# ISD4004.net
KiCad netlist of a schematic drawn in Altium Designer
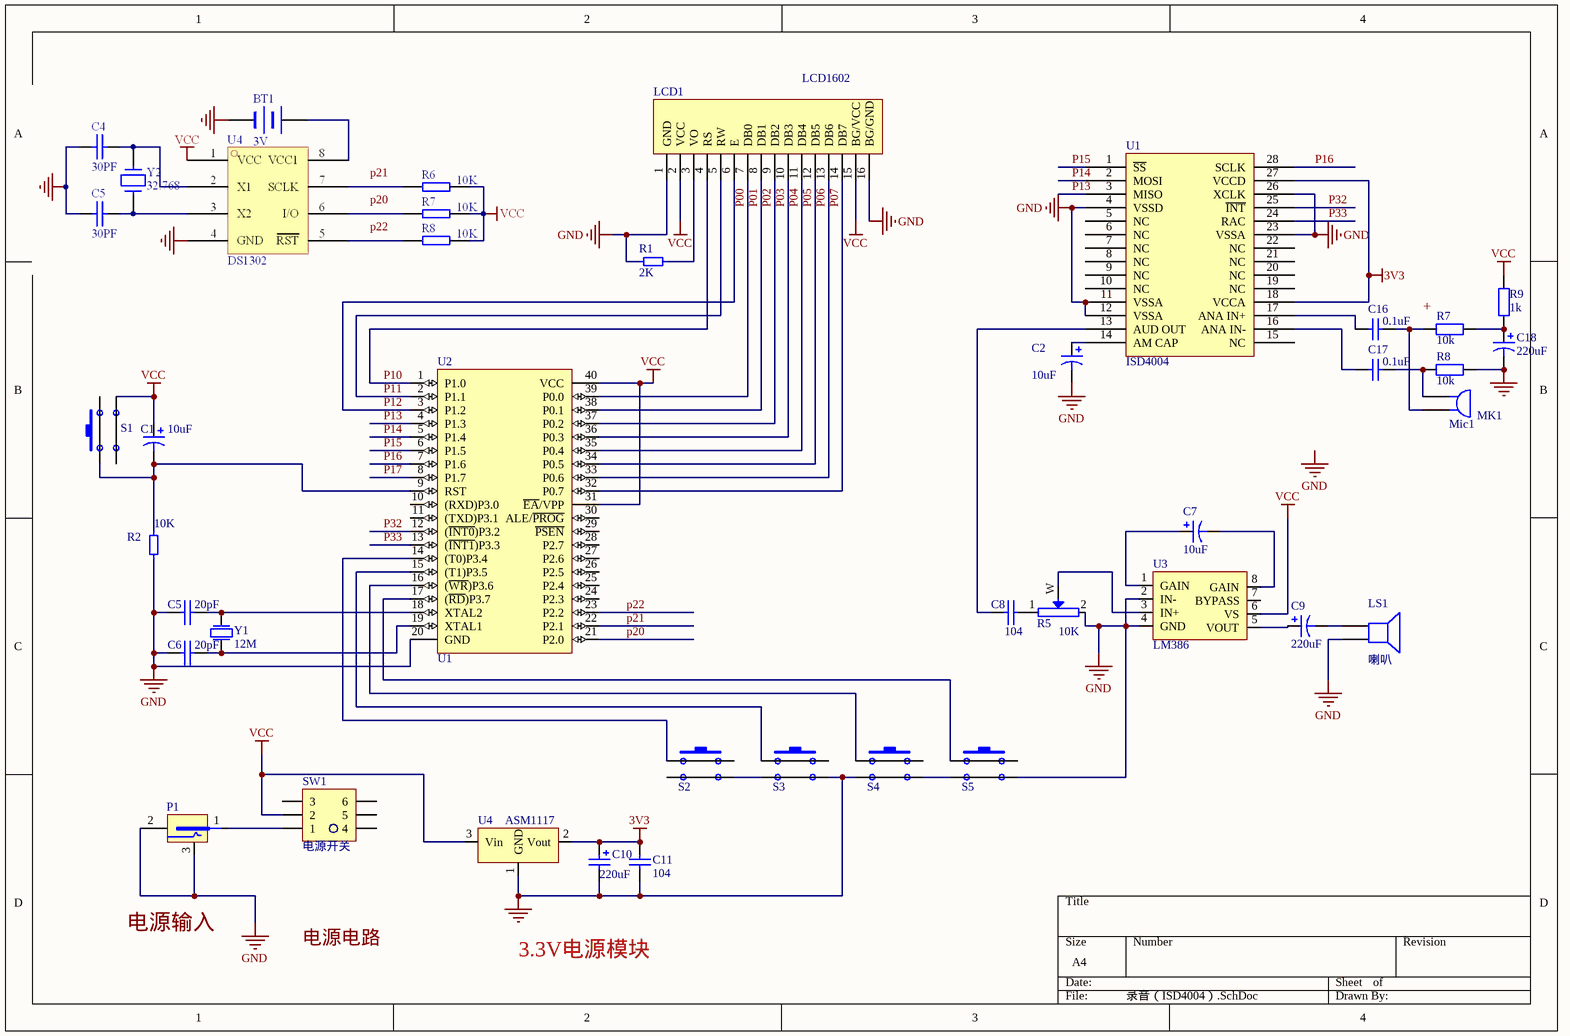
[diagram p0: 录音（ISD4004）.SchDoc]

(export (version "E")
  (design (tool "Eeschema 10.0.6"))
  (components
    (comp (ref "C1")
      (value "10uF")
      (footprint "C_10")
      (description "Polarized Capacitor (Radial)")
      (fields (field (name "PUBLISHER") "Altium Limited"))
      (libsource (lib "简易动环监控系统") (part "Cap Pol1"))
    )
    (comp (ref "C2")
      (value "10uF")
      (footprint "C_10")
      (description "Polarized Capacitor (Radial)")
      (fields (field (name "PUBLISHER") "Altium Limited"))
      (libsource (lib "简易动环监控系统") (part "Cap Pol1"))
    )
    (comp (ref "C5")
      (value "20pF")
      (footprint "CAP CP")
      (description "电容")
      (libsource (lib "C8051F020最小2") (part "CAP"))
    )
    (comp (ref "C6")
      (value "20pF")
      (footprint "CAP CP")
      (description "电容")
      (libsource (lib "C8051F020最小2") (part "CAP"))
    )
    (comp (ref "C7")
      (value "10uF")
      (footprint "CAP_470")
      (description "Polarized Capacitor (Radial)")
      (fields (field (name "PUBLISHER") "Altium Limited"))
      (libsource (lib "简易动环监控系统") (part "Cap Pol1"))
    )
    (comp (ref "C8")
      (value "104")
      (footprint "CAP5")
      (description "电容")
      (libsource (lib "C8051F020最小2") (part "CAP"))
    )
    (comp (ref "C9")
      (value "220uF")
      (footprint "CAP_470")
      (description "Polarized Capacitor (Radial)")
      (fields (field (name "PUBLISHER") "Altium Limited"))
      (libsource (lib "简易动环监控系统") (part "Cap Pol1"))
    )
    (comp (ref "C10")
      (value "220uF")
      (footprint "C_10")
      (description "220uF 470uF 外径8mm 引脚3mm")
      (fields (field (name "Comment") "220uf"))
      (libsource (lib "*") (part "CAP 470uF"))
    )
    (comp (ref "C11")
      (value "104")
      (footprint "CAP CP")
      (description "瓷片电容")
      (libsource (lib "*") (part "CAP"))
    )
    (comp (ref "C16")
      (value "0.1uF")
      (footprint "瓷片电容0.3")
      (description "Capacitor")
      (fields (field (name "PUBLISHER") "Altium Limited"))
      (libsource (lib "Miscellaneous Devices") (part "Cap"))
    )
    (comp (ref "C17")
      (value "0.1uF")
      (footprint "瓷片电容0.3")
      (description "Capacitor")
      (fields (field (name "PUBLISHER") "Altium Limited"))
      (libsource (lib "Miscellaneous Devices") (part "Cap"))
    )
    (comp (ref "C18")
      (value "220uF")
      (footprint "电容0.5")
      (description "Polarized Capacitor (Radial)")
      (fields (field (name "PUBLISHER") "Altium Limited"))
      (libsource (lib "Miscellaneous Devices") (part "Cap Pol1"))
    )
    (comp (ref "LCD1") (value "LCD1602") (footprint "1602") (libsource (lib "实用原理图库") (part "LCD1602")))
    (comp (ref "LS1")
      (value "喇叭")
      (footprint "SIP2")
      (description "Loudspeaker")
      (fields (field (name "PUBLISHER") "Altium Limited"))
      (libsource (lib "Miscellaneous Devices") (part "Speaker"))
    )
    (comp (ref "MK1")
      (value "Mic1")
      (footprint "PIN2")
      (description "Microphone")
      (fields (field (name "PUBLISHER") "Altium Limited"))
      (libsource (lib "Miscellaneous Devices") (part "Mic1"))
    )
    (comp (ref "P1") (value "电源输入") (footprint "DC2.1") (libsource (lib "我自己的") (part "POWER")))
    (comp (ref "R1") (value "2K") (footprint "AXIAL0.3") (libsource (lib "C8051F020最小2") (part "RES2")))
    (comp (ref "R2") (value "10K") (footprint "AXIAL0.3") (libsource (lib "C8051F020最小2") (part "RES2")))
    (comp (ref "R5")
      (value "10K")
      (footprint "RES")
      (description "可调电位器")
      (fields (field (name "Comment") "RES  KB"))
      (libsource (lib "JIANYANG") (part "RES  KB"))
    )
    (comp (ref "R7")
      (value "10k")
      (footprint "AXIAL-0.4")
      (description "Resistor")
      (fields (field (name "PUBLISHER") "Altium Limited"))
      (libsource (lib "") (part "Res2_1"))
    )
    (comp (ref "R8")
      (value "10k")
      (footprint "AXIAL-0.4")
      (description "Resistor")
      (fields (field (name "PUBLISHER") "Altium Limited"))
      (libsource (lib "") (part "Res2_1"))
    )
    (comp (ref "R9")
      (value "1k")
      (footprint "AXIAL-0.4")
      (description "Resistor")
      (fields (field (name "PUBLISHER") "Altium Limited"))
      (libsource (lib "Miscellaneous Devices") (part "Res2"))
    )
    (comp (ref "S1") (value "SW") (footprint "key") (libsource (lib "我自己的") (part "SW1_key")))
    (comp (ref "S2") (value "SW") (footprint "key") (libsource (lib "我自己的") (part "SW1_key")))
    (comp (ref "S3") (value "SW") (footprint "key") (libsource (lib "我自己的") (part "SW1_key")))
    (comp (ref "S4") (value "SW") (footprint "key") (libsource (lib "我自己的") (part "SW1_key")))
    (comp (ref "S5") (value "SW") (footprint "key") (libsource (lib "我自己的") (part "SW1_key")))
    (comp (ref "SW1") (value "电源开关") (footprint "sw_自锁 1") (libsource (lib "我自己的") (part "SW1")))
    (comp (ref "U1") (value "ISD4004") (footprint "DIP28") (libsource (lib "*") (part "ISD4004")))
    (comp (ref "U2") (value "U1") (footprint "DIP40 - 做板") (libsource (lib "实验板原理图") (part "U1")))
    (comp (ref "U3") (value "LM386") (footprint "DIP8") (libsource (lib "我自己的") (part "LM386")))
    (comp (ref "U4") (value "ASM1117") (footprint "ASM1117") (libsource (lib "*") (part "ASM1117")))
    (comp (ref "Y1")
      (value "12M")
      (footprint "XTAL")
      (description "Crystal Oscillator")
      (libsource (lib "C8051F020最小2") (part "16M"))
    )
  )
  (nets
    (net (code "2") (name "/P00") (class "Default")
      (node (ref "LCD1") (pin "7") (pinfunction "DB0_7") (pintype "passive"))
      (node (ref "U2") (pin "39") (pinfunction "P0.0_39") (pintype "bidirectional"))
    )
    (net (code "3") (name "/P01") (class "Default")
      (node (ref "LCD1") (pin "8") (pinfunction "DB1_8") (pintype "passive"))
      (node (ref "U2") (pin "38") (pinfunction "P0.1_38") (pintype "bidirectional"))
    )
    (net (code "4") (name "/P02") (class "Default")
      (node (ref "LCD1") (pin "9") (pinfunction "DB2_9") (pintype "passive"))
      (node (ref "U2") (pin "37") (pinfunction "P0.2_37") (pintype "bidirectional"))
    )
    (net (code "5") (name "/P03") (class "Default")
      (node (ref "LCD1") (pin "10") (pinfunction "DB3_10") (pintype "passive"))
      (node (ref "U2") (pin "36") (pinfunction "P0.3_36") (pintype "bidirectional"))
    )
    (net (code "6") (name "/P04") (class "Default")
      (node (ref "LCD1") (pin "11") (pinfunction "DB4_11") (pintype "passive"))
      (node (ref "U2") (pin "35") (pinfunction "P0.4_35") (pintype "bidirectional"))
    )
    (net (code "7") (name "/P05") (class "Default")
      (node (ref "LCD1") (pin "12") (pinfunction "DB5_12") (pintype "passive"))
      (node (ref "U2") (pin "34") (pinfunction "P0.5_34") (pintype "bidirectional"))
    )
    (net (code "8") (name "/P06") (class "Default")
      (node (ref "LCD1") (pin "13") (pinfunction "DB6_13") (pintype "passive"))
      (node (ref "U2") (pin "33") (pinfunction "P0.6_33") (pintype "bidirectional"))
    )
    (net (code "9") (name "/P07") (class "Default")
      (node (ref "LCD1") (pin "14") (pinfunction "DB7_14") (pintype "passive"))
      (node (ref "U2") (pin "32") (pinfunction "P0.7_32") (pintype "bidirectional"))
    )
    (net (code "10") (name "/P10") (class "Default")
      (node (ref "LCD1") (pin "4") (pinfunction "RS_4") (pintype "passive"))
      (node (ref "U2") (pin "1") (pinfunction "P1.0_1") (pintype "bidirectional"))
    )
    (net (code "11") (name "/P11") (class "Default")
      (node (ref "LCD1") (pin "5") (pinfunction "RW_5") (pintype "passive"))
      (node (ref "U2") (pin "2") (pinfunction "P1.1_2") (pintype "bidirectional"))
    )
    (net (code "12") (name "/P12") (class "Default")
      (node (ref "LCD1") (pin "6") (pinfunction "E_6") (pintype "passive"))
      (node (ref "U2") (pin "3") (pinfunction "P1.2_3") (pintype "bidirectional"))
    )
    (net (code "13") (name "/P13") (class "Default")
      (node (ref "U1") (pin "3") (pinfunction "MISO_3") (pintype "passive"))
      (node (ref "U2") (pin "4") (pinfunction "P1.3_4") (pintype "bidirectional"))
    )
    (net (code "14") (name "/P14") (class "Default")
      (node (ref "U1") (pin "2") (pinfunction "MOSI_2") (pintype "passive"))
      (node (ref "U2") (pin "5") (pinfunction "P1.4_5") (pintype "bidirectional"))
    )
    (net (code "15") (name "/P15") (class "Default")
      (node (ref "U1") (pin "1") (pinfunction "~{SS}_1") (pintype "passive"))
      (node (ref "U2") (pin "6") (pinfunction "P1.5_6") (pintype "bidirectional"))
    )
    (net (code "16") (name "/P16") (class "Default")
      (node (ref "U1") (pin "28") (pinfunction "SCLK_28") (pintype "passive"))
      (node (ref "U2") (pin "7") (pinfunction "P1.6_7") (pintype "bidirectional"))
    )
    (net (code "17") (name "/P17") (class "Default")
      (node (ref "U2") (pin "8") (pinfunction "P1.7_8") (pintype "bidirectional"))
    )
    (net (code "18") (name "/P32") (class "Default")
      (node (ref "U1") (pin "25") (pinfunction "~{INT}_25") (pintype "passive"))
      (node (ref "U2") (pin "12") (pinfunction "(~{INT0})P3.2_12") (pintype "bidirectional"))
    )
    (net (code "19") (name "/P33") (class "Default")
      (node (ref "U1") (pin "24") (pinfunction "RAC_24") (pintype "passive"))
      (node (ref "U2") (pin "13") (pinfunction "(~{INT1})P3.3_13") (pintype "bidirectional"))
    )
    (net (code "20") (name "/p20") (class "Default")
      (node (ref "U2") (pin "21") (pinfunction "P2.0_21") (pintype "bidirectional"))
    )
    (net (code "21") (name "/p21") (class "Default")
      (node (ref "U2") (pin "22") (pinfunction "P2.1_22") (pintype "bidirectional"))
    )
    (net (code "22") (name "/p22") (class "Default")
      (node (ref "U2") (pin "23") (pinfunction "P2.2_23") (pintype "bidirectional"))
    )
    (net (code "25") (name "3V3") (class "Default")
      (node (ref "C10") (pin "1") (pinfunction "1_1") (pintype "passive"))
      (node (ref "C11") (pin "2") (pinfunction "2_2") (pintype "passive"))
      (node (ref "U1") (pin "18") (pinfunction "VCCA_18") (pintype "passive"))
      (node (ref "U1") (pin "27") (pinfunction "VCCD_27") (pintype "passive"))
      (node (ref "U4") (pin "2") (pinfunction "Vout_2") (pintype "passive"))
    )
    (net (code "26") (name "GND") (class "Default")
      (node (ref "C10") (pin "2") (pinfunction "2_2") (pintype "passive"))
      (node (ref "C11") (pin "1") (pinfunction "1_1") (pintype "passive"))
      (node (ref "C18") (pin "2") (pinfunction "2_2") (pintype "passive"))
      (node (ref "C2") (pin "2") (pinfunction "2_2") (pintype "passive"))
      (node (ref "C5") (pin "1") (pinfunction "1_1") (pintype "passive"))
      (node (ref "C6") (pin "1") (pinfunction "1_1") (pintype "passive"))
      (node (ref "LCD1") (pin "1") (pinfunction "GND_1") (pintype "passive"))
      (node (ref "LCD1") (pin "16") (pinfunction "BG/GND_16") (pintype "passive"))
      (node (ref "LS1") (pin "2") (pinfunction "2_2") (pintype "passive"))
      (node (ref "P1") (pin "2") (pintype "passive"))
      (node (ref "P1") (pin "3") (pintype "passive"))
      (node (ref "R1") (pin "1") (pinfunction "1_1") (pintype "passive"))
      (node (ref "R2") (pin "1") (pinfunction "1_1") (pintype "passive"))
      (node (ref "R5") (pin "2") (pintype "passive"))
      (node (ref "R8") (pin "2") (pinfunction "2_2") (pintype "passive"))
      (node (ref "S3") (pin "2") (pinfunction "2_2") (pintype "passive"))
      (node (ref "S4") (pin "2") (pinfunction "2_2") (pintype "passive"))
      (node (ref "S5") (pin "2") (pinfunction "2_2") (pintype "passive"))
      (node (ref "U1") (pin "11") (pinfunction "VSSA_11") (pintype "passive"))
      (node (ref "U1") (pin "12") (pinfunction "VSSA_12") (pintype "passive"))
      (node (ref "U1") (pin "23") (pinfunction "VSSA_23") (pintype "passive"))
      (node (ref "U1") (pin "26") (pinfunction "XCLK_26") (pintype "passive"))
      (node (ref "U1") (pin "4") (pinfunction "VSSD_4") (pintype "passive"))
      (node (ref "U2") (pin "20") (pinfunction "GND_20") (pintype "power_in"))
      (node (ref "U3") (pin "2") (pinfunction "IN-_2") (pintype "passive"))
      (node (ref "U3") (pin "4") (pinfunction "GND_4") (pintype "passive"))
      (node (ref "U4") (pin "1") (pinfunction "GND_1") (pintype "passive"))
    )
    (net (code "27") (name "Net-(C7-Pad1)") (class "Default")
      (node (ref "C7") (pin "1") (pinfunction "1_1") (pintype "passive"))
      (node (ref "U3") (pin "1") (pinfunction "GAIN_1") (pintype "passive"))
    )
    (net (code "28") (name "Net-(C7-Pad2)") (class "Default")
      (node (ref "C7") (pin "2") (pinfunction "2_2") (pintype "passive"))
      (node (ref "U3") (pin "8") (pinfunction "GAIN_8") (pintype "passive"))
    )
    (net (code "29") (name "Net-(C8-Pad2)") (class "Default")
      (node (ref "C8") (pin "2") (pinfunction "2_2") (pintype "passive"))
      (node (ref "R5") (pin "1") (pintype "passive"))
    )
    (net (code "30") (name "Net-(C9-Pad2)") (class "Default")
      (node (ref "C9") (pin "2") (pinfunction "2_2") (pintype "passive"))
      (node (ref "LS1") (pin "1") (pinfunction "1_1") (pintype "passive"))
    )
    (net (code "31") (name "Net-(C16-Pad2)") (class "Default")
      (node (ref "C16") (pin "2") (pinfunction "2_2") (pintype "passive"))
      (node (ref "MK1") (pin "2") (pinfunction "2_2") (pintype "passive"))
      (node (ref "R7") (pin "1") (pinfunction "1_1") (pintype "passive"))
    )
    (net (code "32") (name "Net-(C17-Pad2)") (class "Default")
      (node (ref "C17") (pin "2") (pinfunction "2_2") (pintype "passive"))
      (node (ref "MK1") (pin "1") (pinfunction "1_1") (pintype "passive"))
      (node (ref "R8") (pin "1") (pinfunction "1_1") (pintype "passive"))
    )
    (net (code "33") (name "Net-(C18-Pad1)") (class "Default")
      (node (ref "C18") (pin "1") (pinfunction "1_1") (pintype "passive"))
      (node (ref "R7") (pin "2") (pinfunction "2_2") (pintype "passive"))
      (node (ref "R9") (pin "1") (pinfunction "1_1") (pintype "passive"))
    )
    (net (code "34") (name "Net-(LCD1-VO)") (class "Default")
      (node (ref "LCD1") (pin "3") (pinfunction "VO_3") (pintype "passive"))
      (node (ref "R1") (pin "2") (pinfunction "2_2") (pintype "passive"))
    )
    (net (code "35") (name "Net-(P1-Pad1)") (class "Default")
      (node (ref "P1") (pin "1") (pintype "passive"))
      (node (ref "SW1") (pin "1") (pinfunction "1_1") (pintype "passive"))
    )
    (net (code "36") (name "Net-(S2-Pad2)") (class "Default")
      (node (ref "S2") (pin "2") (pinfunction "2_2") (pintype "passive"))
      (node (ref "S3") (pin "2") (pinfunction "2_2") (pintype "passive"))
    )
    (net (code "37") (name "Net-(S4-Pad2)") (class "Default")
      (node (ref "S4") (pin "2") (pinfunction "2_2") (pintype "passive"))
      (node (ref "S5") (pin "2") (pinfunction "2_2") (pintype "passive"))
    )
    (net (code "38") (name "Net-(U1-AM_CAP)") (class "Default")
      (node (ref "C2") (pin "1") (pinfunction "1_1") (pintype "passive"))
      (node (ref "U1") (pin "14") (pinfunction "AM_CAP_14") (pintype "passive"))
    )
    (net (code "39") (name "Net-(U1-ANA_IN+)") (class "Default")
      (node (ref "C16") (pin "1") (pinfunction "1_1") (pintype "passive"))
      (node (ref "U1") (pin "17") (pinfunction "ANA_IN+_17") (pintype "passive"))
    )
    (net (code "40") (name "Net-(U1-ANA_IN-)") (class "Default")
      (node (ref "C17") (pin "1") (pinfunction "1_1") (pintype "passive"))
      (node (ref "U1") (pin "16") (pinfunction "ANA_IN-_16") (pintype "passive"))
    )
    (net (code "41") (name "Net-(U1-AUD_OUT)") (class "Default")
      (node (ref "C8") (pin "1") (pinfunction "1_1") (pintype "passive"))
      (node (ref "U1") (pin "13") (pinfunction "AUD_OUT_13") (pintype "passive"))
    )
    (net (code "42") (name "Net-(U2-(T0)P3.4)") (class "Default")
      (node (ref "S2") (pin "1") (pinfunction "1_1") (pintype "passive"))
      (node (ref "U2") (pin "14") (pinfunction "(T0)P3.4_14") (pintype "bidirectional"))
    )
    (net (code "43") (name "Net-(U2-(T1)P3.5)") (class "Default")
      (node (ref "S3") (pin "1") (pinfunction "1_1") (pintype "passive"))
      (node (ref "U2") (pin "15") (pinfunction "(T1)P3.5_15") (pintype "bidirectional"))
    )
    (net (code "44") (name "Net-(U2-(~{RD})P3.7)") (class "Default")
      (node (ref "S5") (pin "1") (pinfunction "1_1") (pintype "passive"))
      (node (ref "U2") (pin "17") (pinfunction "(~{RD})P3.7_17") (pintype "bidirectional"))
    )
    (net (code "45") (name "Net-(U2-(~{WR})P3.6)") (class "Default")
      (node (ref "S4") (pin "1") (pinfunction "1_1") (pintype "passive"))
      (node (ref "U2") (pin "16") (pinfunction "(~{WR})P3.6_16") (pintype "bidirectional"))
    )
    (net (code "46") (name "Net-(U2-RST)") (class "Default")
      (node (ref "C1") (pin "2") (pinfunction "2_2") (pintype "passive"))
      (node (ref "R2") (pin "2") (pinfunction "2_2") (pintype "passive"))
      (node (ref "S1") (pin "1") (pinfunction "1_1") (pintype "passive"))
      (node (ref "U2") (pin "9") (pinfunction "RST_9") (pintype "bidirectional"))
    )
    (net (code "47") (name "Net-(U2-XTAL1)") (class "Default")
      (node (ref "C6") (pin "2") (pinfunction "2_2") (pintype "passive"))
      (node (ref "U2") (pin "19") (pinfunction "XTAL1_19") (pintype "bidirectional"))
      (node (ref "Y1") (pin "2") (pinfunction "P2_2") (pintype "passive"))
    )
    (net (code "48") (name "Net-(U2-XTAL2)") (class "Default")
      (node (ref "C5") (pin "2") (pinfunction "2_2") (pintype "passive"))
      (node (ref "U2") (pin "18") (pinfunction "XTAL2_18") (pintype "bidirectional"))
      (node (ref "Y1") (pin "1") (pinfunction "P1_1") (pintype "passive"))
    )
    (net (code "49") (name "Net-(U3-IN+)") (class "Default")
      (node (ref "R5") (pin "W") (pintype "passive"))
      (node (ref "U3") (pin "3") (pinfunction "IN+_3") (pintype "passive"))
    )
    (net (code "50") (name "Net-(U3-VOUT)") (class "Default")
      (node (ref "C9") (pin "1") (pinfunction "1_1") (pintype "passive"))
      (node (ref "U3") (pin "5") (pinfunction "VOUT_5") (pintype "passive"))
    )
    (net (code "51") (name "VCC") (class "Default")
      (node (ref "C1") (pin "1") (pinfunction "1_1") (pintype "passive"))
      (node (ref "LCD1") (pin "15") (pinfunction "BG/VCC_15") (pintype "passive"))
      (node (ref "LCD1") (pin "2") (pinfunction "VCC_2") (pintype "passive"))
      (node (ref "R9") (pin "2") (pinfunction "2_2") (pintype "passive"))
      (node (ref "S1") (pin "2") (pinfunction "2_2") (pintype "passive"))
      (node (ref "SW1") (pin "2") (pinfunction "2_2") (pintype "passive"))
      (node (ref "U2") (pin "31") (pinfunction "~{EA}/VPP_31") (pintype "power_in"))
      (node (ref "U2") (pin "40") (pinfunction "VCC_40") (pintype "power_in"))
      (node (ref "U3") (pin "6") (pinfunction "VS_6") (pintype "passive"))
      (node (ref "U4") (pin "3") (pinfunction "Vin_3") (pintype "passive"))
    )
    (net (code "52") (name "unconnected-(S1-Pad1)") (class "Default")
      (node (ref "S1") (pin "1") (pinfunction "1_1") (pintype "passive"))
    )
    (net (code "53") (name "unconnected-(S1-Pad2)") (class "Default")
      (node (ref "S1") (pin "2") (pinfunction "2_2") (pintype "passive"))
    )
    (net (code "54") (name "unconnected-(S2-Pad1)") (class "Default")
      (node (ref "S2") (pin "1") (pinfunction "1_1") (pintype "passive"))
    )
    (net (code "55") (name "unconnected-(S2-Pad2)_1") (class "Default")
      (node (ref "S2") (pin "2") (pinfunction "2_2") (pintype "passive"))
    )
    (net (code "56") (name "unconnected-(S3-Pad1)") (class "Default")
      (node (ref "S3") (pin "1") (pinfunction "1_1") (pintype "passive"))
    )
    (net (code "57") (name "unconnected-(S4-Pad1)") (class "Default")
      (node (ref "S4") (pin "1") (pinfunction "1_1") (pintype "passive"))
    )
    (net (code "58") (name "unconnected-(S5-Pad1)") (class "Default")
      (node (ref "S5") (pin "1") (pinfunction "1_1") (pintype "passive"))
    )
    (net (code "59") (name "unconnected-(SW1-Pad3)") (class "Default")
      (node (ref "SW1") (pin "3") (pinfunction "3_3") (pintype "passive"))
    )
    (net (code "60") (name "unconnected-(SW1-Pad4)") (class "Default")
      (node (ref "SW1") (pin "4") (pinfunction "4_4") (pintype "passive"))
    )
    (net (code "61") (name "unconnected-(SW1-Pad5)") (class "Default")
      (node (ref "SW1") (pin "5") (pinfunction "5_5") (pintype "passive"))
    )
    (net (code "62") (name "unconnected-(SW1-Pad6)") (class "Default")
      (node (ref "SW1") (pin "6") (pinfunction "6_6") (pintype "passive"))
    )
    (net (code "63") (name "unconnected-(U1-NC-Pad5)") (class "Default")
      (node (ref "U1") (pin "5") (pinfunction "NC_5") (pintype "passive"))
    )
    (net (code "64") (name "unconnected-(U1-NC-Pad6)") (class "Default")
      (node (ref "U1") (pin "6") (pinfunction "NC_6") (pintype "passive"))
    )
    (net (code "65") (name "unconnected-(U1-NC-Pad7)") (class "Default")
      (node (ref "U1") (pin "7") (pinfunction "NC_7") (pintype "passive"))
    )
    (net (code "66") (name "unconnected-(U1-NC-Pad8)") (class "Default")
      (node (ref "U1") (pin "8") (pinfunction "NC_8") (pintype "passive"))
    )
    (net (code "67") (name "unconnected-(U1-NC-Pad9)") (class "Default")
      (node (ref "U1") (pin "9") (pinfunction "NC_9") (pintype "passive"))
    )
    (net (code "68") (name "unconnected-(U1-NC-Pad10)") (class "Default")
      (node (ref "U1") (pin "10") (pinfunction "NC_10") (pintype "passive"))
    )
    (net (code "69") (name "unconnected-(U1-NC-Pad15)") (class "Default")
      (node (ref "U1") (pin "15") (pinfunction "NC_15") (pintype "passive"))
    )
    (net (code "70") (name "unconnected-(U1-NC-Pad19)") (class "Default")
      (node (ref "U1") (pin "19") (pinfunction "NC_19") (pintype "passive"))
    )
    (net (code "71") (name "unconnected-(U1-NC-Pad20)") (class "Default")
      (node (ref "U1") (pin "20") (pinfunction "NC_20") (pintype "passive"))
    )
    (net (code "72") (name "unconnected-(U1-NC-Pad21)") (class "Default")
      (node (ref "U1") (pin "21") (pinfunction "NC_21") (pintype "passive"))
    )
    (net (code "73") (name "unconnected-(U1-NC-Pad22)") (class "Default")
      (node (ref "U1") (pin "22") (pinfunction "NC_22") (pintype "passive"))
    )
    (net (code "74") (name "unconnected-(U2-(RXD)P3.0-Pad10)") (class "Default")
      (node (ref "U2") (pin "10") (pinfunction "(RXD)P3.0_10") (pintype "bidirectional"))
    )
    (net (code "75") (name "unconnected-(U2-(TXD)P3.1-Pad11)") (class "Default")
      (node (ref "U2") (pin "11") (pinfunction "(TXD)P3.1_11") (pintype "bidirectional"))
    )
    (net (code "76") (name "unconnected-(U2-ALE{slash}~{PROG}-Pad30)") (class "Default")
      (node (ref "U2") (pin "30") (pinfunction "ALE/~{PROG}_30") (pintype "bidirectional"))
    )
    (net (code "77") (name "unconnected-(U2-P2.3-Pad24)") (class "Default")
      (node (ref "U2") (pin "24") (pinfunction "P2.3_24") (pintype "bidirectional"))
    )
    (net (code "78") (name "unconnected-(U2-P2.4-Pad25)") (class "Default")
      (node (ref "U2") (pin "25") (pinfunction "P2.4_25") (pintype "bidirectional"))
    )
    (net (code "79") (name "unconnected-(U2-P2.5-Pad26)") (class "Default")
      (node (ref "U2") (pin "26") (pinfunction "P2.5_26") (pintype "bidirectional"))
    )
    (net (code "80") (name "unconnected-(U2-P2.6-Pad27)") (class "Default")
      (node (ref "U2") (pin "27") (pinfunction "P2.6_27") (pintype "bidirectional"))
    )
    (net (code "81") (name "unconnected-(U2-P2.7-Pad28)") (class "Default")
      (node (ref "U2") (pin "28") (pinfunction "P2.7_28") (pintype "bidirectional"))
    )
    (net (code "82") (name "unconnected-(U2-~{PSEN}-Pad29)") (class "Default")
      (node (ref "U2") (pin "29") (pinfunction "~{PSEN}_29") (pintype "bidirectional"))
    )
    (net (code "83") (name "unconnected-(U3-BYPASS-Pad7)") (class "Default")
      (node (ref "U3") (pin "7") (pinfunction "BYPASS_7") (pintype "passive"))
    )
  )
)
